# Peripherals.net
KiCad netlist of a schematic drawn in Altium Designer
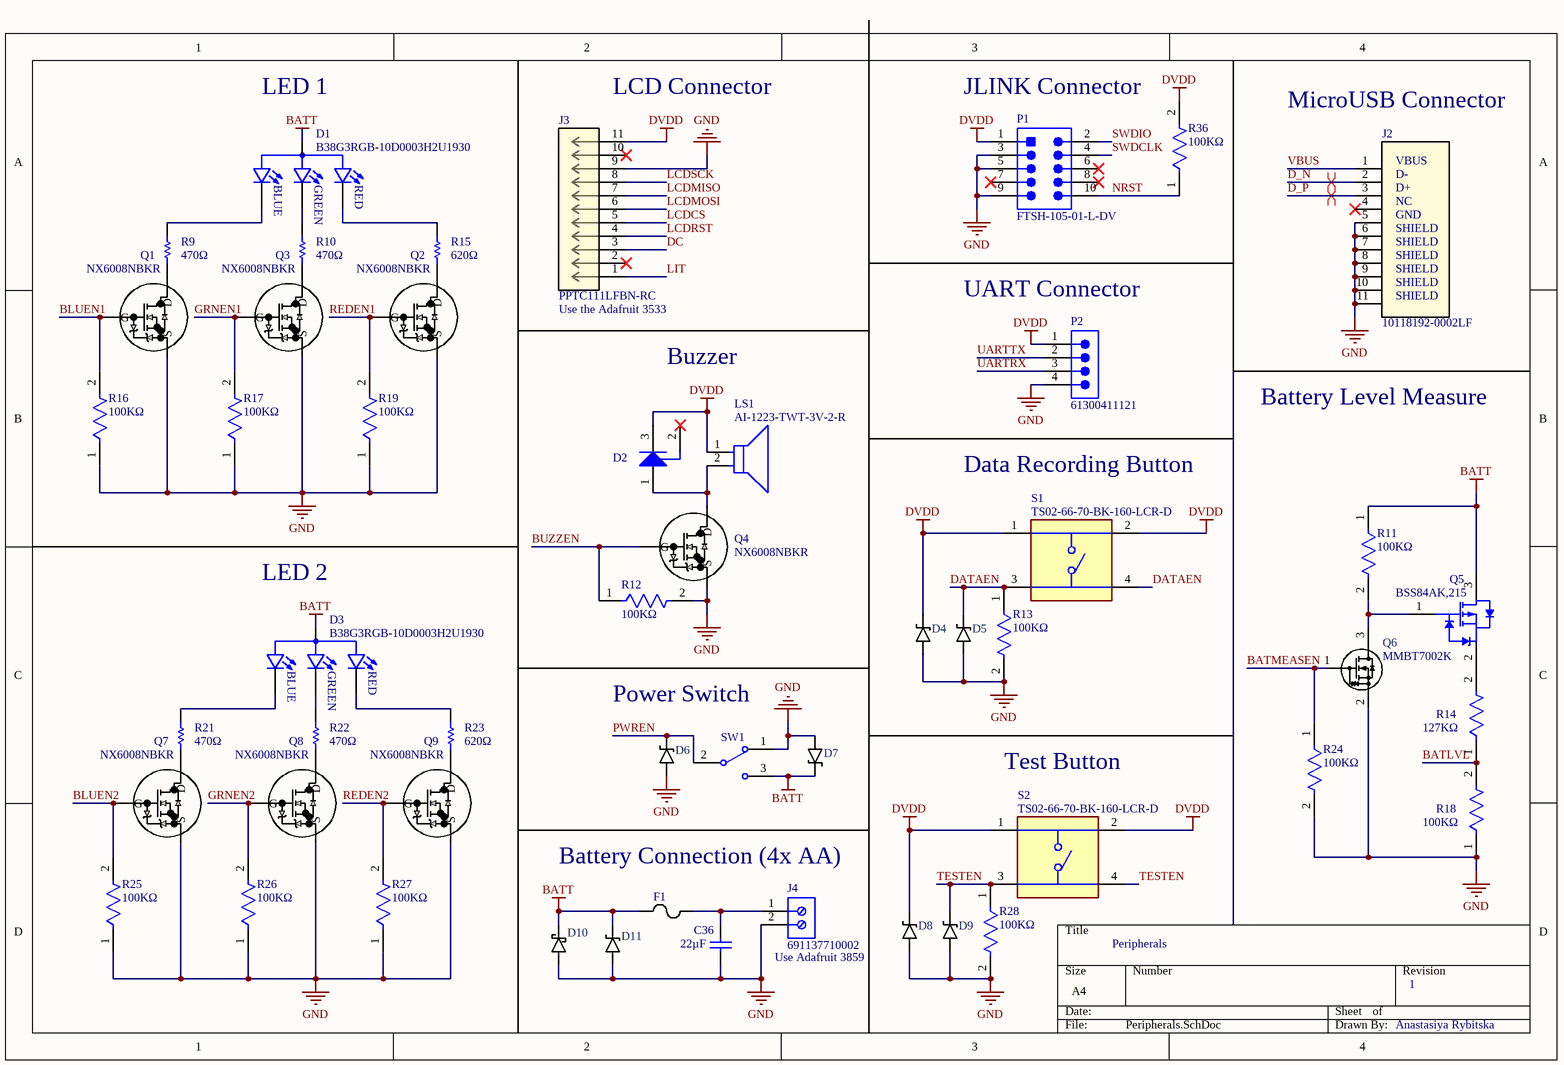
[diagram p0: Peripherals.SchDoc]

(export (version "E")
  (design (tool "Eeschema 10.0.6"))
  (components
    (comp (ref "C36")
      (value "TCJA226M016R0300E")
      (footprint "KEMT-1206-2_M")
      (description "CAP TANT POLY 22UF 16V 1206")
      (fields (field (name "CAPACITANCE") "22µF") (field (name "MANUFACTURER") "Kemet"))
      (libsource (lib "Altium Content Vault") (part "CAP-NP-2"))
    )
    (comp (ref "D1")
      (value "B38G3RGB-10D0003H2U1930")
      (footprint "LED_B38G3RGB-10D0003H2U1930")
      (description "Red, Green, Blue (RGB) - LED Indication - Discrete 2V Red, 3V Green, 3V Blue 0606 (1616 Metric)")
      (fields (field (name "MF") "Harvatek Corporation"))
      (libsource (lib "Schlib1") (part "B38G3RGB-10D0003H2U1930"))
    )
    (comp (ref "D2")
      (value "BAS16LT1G")
      (footprint "ONSC-SOT-23-3-318-08_V")
      (description "Switching Diode, 3-Pin SOT-23, Pb-Free, Tape and Reel")
      (fields (field (name "MANUFACTURER") "On Semiconductor"))
      (libsource (lib "Altium Content Vault") (part "ONSC-D-A1K3-3"))
    )
    (comp (ref "D3")
      (value "B38G3RGB-10D0003H2U1930")
      (footprint "LED_B38G3RGB-10D0003H2U1930")
      (description "Red, Green, Blue (RGB) - LED Indication - Discrete 2V Red, 3V Green, 3V Blue 0606 (1616 Metric)")
      (fields (field (name "MF") "Harvatek Corporation"))
      (libsource (lib "Schlib1") (part "B38G3RGB-10D0003H2U1930"))
    )
    (comp (ref "D4") (value "ESD5Z3V3") (footprint "SOD-523") (libsource (lib "Schlib1") (part "ESD5Z3V3")))
    (comp (ref "D5") (value "ESD5Z3V3") (footprint "SOD-523") (libsource (lib "Schlib1") (part "ESD5Z3V3")))
    (comp (ref "D6") (value "ESD5Z3V3") (footprint "SOD-523") (libsource (lib "Schlib1") (part "ESD5Z3V3")))
    (comp (ref "D7") (value "ESD5Z3V3") (footprint "SOD-523") (libsource (lib "Schlib1") (part "ESD5Z3V3")))
    (comp (ref "D8") (value "ESD5Z3V3") (footprint "SOD-523") (libsource (lib "Schlib1") (part "ESD5Z3V3")))
    (comp (ref "D9") (value "ESD5Z3V3") (footprint "SOD-523") (libsource (lib "Schlib1") (part "ESD5Z3V3")))
    (comp (ref "D10") (value "SK16") (footprint "DO-214AC_SMA") (libsource (lib "Schlib1") (part "SK16")))
    (comp (ref "D11") (value "ESD5Z3V3") (footprint "SOD-523") (libsource (lib "Schlib1") (part "ESD5Z3V3")))
    (comp (ref "F1")
      (value "MFU0603FF02000P500")
      (footprint "FUS_VISHAY_MFU0603_VIS")
      (description "No Description Available")
      (fields (field (name "COPYRIGHT") "Copyright (C) 2024 Ultra Librarian. All rights reserved."))
      (libsource (lib "Schlib1") (part "MFU0603FF02000P500"))
    )
    (comp (ref "J2")
      (value "10118192-0002LF")
      (footprint "CONN_10118192-0002LF_AMP")
      (description "No Description Available")
      (fields (field (name "COPYRIGHT") "Copyright (C) 2024 Ultra Librarian. All rights reserved."))
      (libsource (lib "Schlib1") (part "10118192-0002LF"))
    )
    (comp (ref "J3")
      (value "PPTC111LFBN-RC")
      (footprint "CONN11_PPPN111_SUL")
      (description "No Description Available")
      (fields (field (name "COPYRIGHT") "Copyright (C) 2023 Ultra Librarian. All rights reserved."))
      (libsource (lib "Schlib1") (part "PPTC111LFBN-RC"))
    )
    (comp (ref "J4")
      (value "691137710002")
      (footprint "691137710002")
      (libsource (lib "Altium Content Vault") (part "TBL - 1R - 02P - Screw"))
    )
    (comp (ref "LS1")
      (value "AI-1223-TWT-3V-2-R")
      (footprint "FP-AI-1223-TWT-3V-2-R-MFG")
      (description "BUZZER MAGNETIC 3V 12MM TH")
      (libsource (lib "Altium Content Vault") (part "1973c4b650225fd2ddacaff6b763965"))
    )
    (comp (ref "P1")
      (value "FTSH-105-01-L-DV")
      (footprint "SMTC-FTSH-105-01-L-DV_V")
      (description "CONN HEADER SMD 10POS 1.27MM (get from Garmin, or order cheaper)")
      (fields (field (name "MANUFACTURER") "Samtec"))
      (libsource (lib "Altium Content Vault") (part "CN-2P-M-R10"))
    )
    (comp (ref "P2")
      (value "61300411121")
      (footprint "61300411121")
      (libsource (lib "Altium Content Vault") (part "Header_Male_1R_04P"))
    )
    (comp (ref "Q1")
      (value "NX6008NBKR")
      (footprint "NX6008NBKR_NEX")
      (description "No Description Available")
      (fields (field (name "COPYRIGHT") "Copyright (C) 2023 Ultra Librarian. All rights reserved."))
      (libsource (lib "Schlib1") (part "NX6008NBKR"))
    )
    (comp (ref "Q2")
      (value "NX6008NBKR")
      (footprint "NX6008NBKR_NEX")
      (description "No Description Available")
      (fields (field (name "COPYRIGHT") "Copyright (C) 2023 Ultra Librarian. All rights reserved."))
      (libsource (lib "Schlib1") (part "NX6008NBKR"))
    )
    (comp (ref "Q3")
      (value "NX6008NBKR")
      (footprint "NX6008NBKR_NEX")
      (description "No Description Available")
      (fields (field (name "COPYRIGHT") "Copyright (C) 2023 Ultra Librarian. All rights reserved."))
      (libsource (lib "Schlib1") (part "NX6008NBKR"))
    )
    (comp (ref "Q4")
      (value "NX6008NBKR")
      (footprint "NX6008NBKR_NEX")
      (description "No Description Available")
      (fields (field (name "COPYRIGHT") "Copyright (C) 2023 Ultra Librarian. All rights reserved."))
      (libsource (lib "Schlib1") (part "NX6008NBKR"))
    )
    (comp (ref "Q5")
      (value "BSS84AK,215")
      (footprint "NXP-SOT23_N")
      (description "P-Channel Trench MOSFET, -50 V, -0.18 A, -55 to 150 degC, 3-Pin SOT23, Tape and Reel")
      (fields (field (name "MANUFACTURER") "NXP Semiconductors"))
      (libsource (lib "Altium Content Vault") (part "NXP-PMOS-GSD-3_B"))
    )
    (comp (ref "Q6") (value "MMBT7002K") (footprint "SOT-23") (libsource (lib "Schlib1") (part "MMBT7002K")))
    (comp (ref "Q7")
      (value "NX6008NBKR")
      (footprint "NX6008NBKR_NEX")
      (description "No Description Available")
      (fields (field (name "COPYRIGHT") "Copyright (C) 2023 Ultra Librarian. All rights reserved."))
      (libsource (lib "Schlib1") (part "NX6008NBKR"))
    )
    (comp (ref "Q8")
      (value "NX6008NBKR")
      (footprint "NX6008NBKR_NEX")
      (description "No Description Available")
      (fields (field (name "COPYRIGHT") "Copyright (C) 2023 Ultra Librarian. All rights reserved."))
      (libsource (lib "Schlib1") (part "NX6008NBKR"))
    )
    (comp (ref "Q9")
      (value "NX6008NBKR")
      (footprint "NX6008NBKR_NEX")
      (description "No Description Available")
      (fields (field (name "COPYRIGHT") "Copyright (C) 2023 Ultra Librarian. All rights reserved."))
      (libsource (lib "Schlib1") (part "NX6008NBKR"))
    )
    (comp (ref "R9")
      (value "RC0603FR-13470RL")
      (footprint "RESC1608X55X25NL10T15")
      (fields (field (name "MANUFACTURER") "Yageo") (field (name "RESISTANCE") "470Ω"))
      (libsource (lib "Altium Content Vault") (part "RES"))
    )
    (comp (ref "R10")
      (value "RC0603FR-13470RL")
      (footprint "RESC1608X55X25NL10T15")
      (fields (field (name "MANUFACTURER") "Yageo") (field (name "RESISTANCE") "470Ω"))
      (libsource (lib "Altium Content Vault") (part "RES"))
    )
    (comp (ref "R11")
      (value "RMCF0603FT100K")
      (footprint "FP-RMCF0603-IPC_C")
      (description "100kΩ ±1% 0.1W 0603 Thick Film Chip Resistor AEC-Q200 compliant")
      (fields (field (name "TOLERANCE") "1%") (field (name "RESISTANCE") "100KΩ"))
      (libsource (lib "Altium Content Vault") (part "1029c3af85768c4190bb7ad29bc67b5"))
    )
    (comp (ref "R12")
      (value "RMCF0603FT100K")
      (footprint "FP-RMCF0603-IPC_C")
      (description "100kΩ ±1% 0.1W 0603 Thick Film Chip Resistor AEC-Q200 compliant")
      (fields (field (name "TOLERANCE") "1%") (field (name "RESISTANCE") "100KΩ"))
      (libsource (lib "Altium Content Vault") (part "1029c3af85768c4190bb7ad29bc67b5"))
    )
    (comp (ref "R13")
      (value "RMCF0603FT100K")
      (footprint "FP-RMCF0603-IPC_C")
      (description "100kΩ ±1% 0.1W 0603 Thick Film Chip Resistor AEC-Q200 compliant")
      (fields (field (name "TOLERANCE") "1%") (field (name "RESISTANCE") "100KΩ"))
      (libsource (lib "Altium Content Vault") (part "1029c3af85768c4190bb7ad29bc67b5"))
    )
    (comp (ref "R14")
      (value "RT0603FRE07127KL")
      (footprint "FP-RT0603-MFG")
      (description "RES SMD 127K OHM 1% 1/10W 0603")
      (fields
        (field (name "MANUFACTURER") "Yageo")
        (field (name "TOLERANCE") "0.01")
        (field (name "RESISTANCE") "127KΩ")
      )
      (libsource (lib "Altium Content Vault") (part "1029c3af85768c4190bb7ad29bc67b5"))
    )
    (comp (ref "R15")
      (value "RC0603JR-07620RL")
      (footprint "RESC1608X55X25LL10T15")
      (fields (field (name "MANUFACTURER") "Yageo") (field (name "RESISTANCE") "620Ω"))
      (libsource (lib "Altium Content Vault") (part "RES"))
    )
    (comp (ref "R16")
      (value "RMCF0603FT100K")
      (footprint "FP-RMCF0603-IPC_C")
      (description "100kΩ ±1% 0.1W 0603 Thick Film Chip Resistor AEC-Q200 compliant")
      (fields (field (name "TOLERANCE") "1%") (field (name "RESISTANCE") "100KΩ"))
      (libsource (lib "Altium Content Vault") (part "1029c3af85768c4190bb7ad29bc67b5"))
    )
    (comp (ref "R17")
      (value "RMCF0603FT100K")
      (footprint "FP-RMCF0603-IPC_C")
      (description "100kΩ ±1% 0.1W 0603 Thick Film Chip Resistor AEC-Q200 compliant")
      (fields (field (name "TOLERANCE") "1%") (field (name "RESISTANCE") "100KΩ"))
      (libsource (lib "Altium Content Vault") (part "1029c3af85768c4190bb7ad29bc67b5"))
    )
    (comp (ref "R18")
      (value "RMCF0603FT100K")
      (footprint "FP-RMCF0603-IPC_C")
      (description "100kΩ ±1% 0.1W 0603 Thick Film Chip Resistor AEC-Q200 compliant")
      (fields (field (name "TOLERANCE") "1%") (field (name "RESISTANCE") "100KΩ"))
      (libsource (lib "Altium Content Vault") (part "1029c3af85768c4190bb7ad29bc67b5"))
    )
    (comp (ref "R19")
      (value "RMCF0603FT100K")
      (footprint "FP-RMCF0603-IPC_C")
      (description "100kΩ ±1% 0.1W 0603 Thick Film Chip Resistor AEC-Q200 compliant")
      (fields (field (name "TOLERANCE") "1%") (field (name "RESISTANCE") "100KΩ"))
      (libsource (lib "Altium Content Vault") (part "1029c3af85768c4190bb7ad29bc67b5"))
    )
    (comp (ref "R21")
      (value "RC0603FR-13470RL")
      (footprint "RESC1608X55X25NL10T15")
      (fields (field (name "MANUFACTURER") "Yageo") (field (name "RESISTANCE") "470Ω"))
      (libsource (lib "Altium Content Vault") (part "RES"))
    )
    (comp (ref "R22")
      (value "RC0603FR-13470RL")
      (footprint "RESC1608X55X25NL10T15")
      (fields (field (name "MANUFACTURER") "Yageo") (field (name "RESISTANCE") "470Ω"))
      (libsource (lib "Altium Content Vault") (part "RES"))
    )
    (comp (ref "R23")
      (value "RC0603JR-07620RL")
      (footprint "RESC1608X55X25LL10T15")
      (fields (field (name "MANUFACTURER") "Yageo") (field (name "RESISTANCE") "620Ω"))
      (libsource (lib "Altium Content Vault") (part "RES"))
    )
    (comp (ref "R24")
      (value "RMCF0603FT100K")
      (footprint "FP-RMCF0603-IPC_C")
      (description "100kΩ ±1% 0.1W 0603 Thick Film Chip Resistor AEC-Q200 compliant")
      (fields (field (name "TOLERANCE") "1%") (field (name "RESISTANCE") "100KΩ"))
      (libsource (lib "Altium Content Vault") (part "1029c3af85768c4190bb7ad29bc67b5"))
    )
    (comp (ref "R25")
      (value "RMCF0603FT100K")
      (footprint "FP-RMCF0603-IPC_C")
      (description "100kΩ ±1% 0.1W 0603 Thick Film Chip Resistor AEC-Q200 compliant")
      (fields (field (name "TOLERANCE") "1%") (field (name "RESISTANCE") "100KΩ"))
      (libsource (lib "Altium Content Vault") (part "1029c3af85768c4190bb7ad29bc67b5"))
    )
    (comp (ref "R26")
      (value "RMCF0603FT100K")
      (footprint "FP-RMCF0603-IPC_C")
      (description "100kΩ ±1% 0.1W 0603 Thick Film Chip Resistor AEC-Q200 compliant")
      (fields (field (name "TOLERANCE") "1%") (field (name "RESISTANCE") "100KΩ"))
      (libsource (lib "Altium Content Vault") (part "1029c3af85768c4190bb7ad29bc67b5"))
    )
    (comp (ref "R27")
      (value "RMCF0603FT100K")
      (footprint "FP-RMCF0603-IPC_C")
      (description "100kΩ ±1% 0.1W 0603 Thick Film Chip Resistor AEC-Q200 compliant")
      (fields (field (name "TOLERANCE") "1%") (field (name "RESISTANCE") "100KΩ"))
      (libsource (lib "Altium Content Vault") (part "1029c3af85768c4190bb7ad29bc67b5"))
    )
    (comp (ref "R28")
      (value "RMCF0603FT100K")
      (footprint "FP-RMCF0603-IPC_C")
      (description "100kΩ ±1% 0.1W 0603 Thick Film Chip Resistor AEC-Q200 compliant")
      (fields (field (name "TOLERANCE") "1%") (field (name "RESISTANCE") "100KΩ"))
      (libsource (lib "Altium Content Vault") (part "1029c3af85768c4190bb7ad29bc67b5"))
    )
    (comp (ref "R36")
      (value "RMCF0603FT100K")
      (footprint "FP-RMCF0603-IPC_C")
      (description "100kΩ ±1% 0.1W 0603 Thick Film Chip Resistor AEC-Q200 compliant")
      (fields (field (name "TOLERANCE") "1%") (field (name "RESISTANCE") "100KΩ"))
      (libsource (lib "Altium Content Vault") (part "1029c3af85768c4190bb7ad29bc67b5"))
    )
    (comp (ref "S1")
      (value "TS02-66-70-BK-160-LCR-D")
      (footprint "SW_TS02-66-70-BK-160-LCR-D")
      (description "6 x 6 mm, 7 mm Actuator Height, 160 gf, Black, Long Crimped, Through Hole, SPST, Tactile Switch")
      (fields (field (name "MF") "CUI Devices"))
      (libsource (lib "Schlib1") (part "TS02-66-70-BK-160-LCR-D"))
    )
    (comp (ref "S2")
      (value "TS02-66-70-BK-160-LCR-D")
      (footprint "SW_TS02-66-70-BK-160-LCR-D")
      (description "6 x 6 mm, 7 mm Actuator Height, 160 gf, Black, Long Crimped, Through Hole, SPST, Tactile Switch")
      (fields (field (name "MF") "CUI Devices"))
      (libsource (lib "Schlib1") (part "TS02-66-70-BK-160-LCR-D"))
    )
    (comp (ref "SW1")
      (value "EG1218")
      (footprint "ESWI-EG1218_V")
      (description "Slide Switch, 500 V, -20 to 70 degC, 3-Pin THD, RoHS")
      (libsource (lib "Altium Content Vault") (part "SW-SPDT-3_B"))
    )
  )
  (nets
    (net (code "1") (name "/BATLVL") (class "Default")
      (node (ref "R14") (pin "1") (pinfunction "1_1") (pintype "passive"))
      (node (ref "R18") (pin "2") (pinfunction "2_2") (pintype "passive"))
    )
    (net (code "2") (name "/BATMEASEN") (class "Default")
      (node (ref "Q6") (pin "1") (pinfunction "G_1") (pintype "passive"))
      (node (ref "R24") (pin "1") (pinfunction "1_1") (pintype "passive"))
    )
    (net (code "3") (name "/BLUEN1") (class "Default")
      (node (ref "Q1") (pin "1") (pinfunction "G_1") (pintype "passive"))
      (node (ref "R16") (pin "2") (pinfunction "2_2") (pintype "passive"))
    )
    (net (code "4") (name "/BLUEN2") (class "Default")
      (node (ref "Q7") (pin "1") (pinfunction "G_1") (pintype "passive"))
      (node (ref "R25") (pin "2") (pinfunction "2_2") (pintype "passive"))
    )
    (net (code "5") (name "/BUZZEN") (class "Default")
      (node (ref "Q4") (pin "1") (pinfunction "G_1") (pintype "passive"))
      (node (ref "R12") (pin "1") (pinfunction "1_1") (pintype "passive"))
    )
    (net (code "6") (name "/DATAEN") (class "Default")
      (node (ref "D5") (pin "K") (pinfunction "K_K") (pintype "passive"))
      (node (ref "R13") (pin "1") (pinfunction "1_1") (pintype "passive"))
      (node (ref "S1") (pin "3") (pinfunction "3_3") (pintype "passive"))
      (node (ref "S1") (pin "4") (pinfunction "4_4") (pintype "passive"))
    )
    (net (code "7") (name "/DC") (class "Default")
      (node (ref "J3") (pin "3") (pinfunction "3_3") (pintype "passive"))
    )
    (net (code "8") (name "/D_N") (class "Default")
      (node (ref "J2") (pin "2") (pinfunction "2_2") (pintype "passive"))
    )
    (net (code "9") (name "/D_P") (class "Default")
      (node (ref "J2") (pin "3") (pinfunction "3_3") (pintype "passive"))
    )
    (net (code "10") (name "/GRNEN1") (class "Default")
      (node (ref "Q3") (pin "1") (pinfunction "G_1") (pintype "passive"))
      (node (ref "R17") (pin "2") (pinfunction "2_2") (pintype "passive"))
    )
    (net (code "11") (name "/GRNEN2") (class "Default")
      (node (ref "Q8") (pin "1") (pinfunction "G_1") (pintype "passive"))
      (node (ref "R26") (pin "2") (pinfunction "2_2") (pintype "passive"))
    )
    (net (code "12") (name "/LCDCS") (class "Default")
      (node (ref "J3") (pin "5") (pinfunction "5_5") (pintype "passive"))
    )
    (net (code "13") (name "/LCDMISO") (class "Default")
      (node (ref "J3") (pin "7") (pinfunction "7_7") (pintype "passive"))
    )
    (net (code "14") (name "/LCDMOSI") (class "Default")
      (node (ref "J3") (pin "6") (pinfunction "6_6") (pintype "passive"))
    )
    (net (code "15") (name "/LCDRST") (class "Default")
      (node (ref "J3") (pin "4") (pinfunction "4_4") (pintype "passive"))
    )
    (net (code "16") (name "/LCDSCK") (class "Default")
      (node (ref "J3") (pin "8") (pinfunction "8_8") (pintype "passive"))
    )
    (net (code "17") (name "/LIT") (class "Default")
      (node (ref "J3") (pin "1") (pinfunction "1_1") (pintype "passive"))
    )
    (net (code "18") (name "/NRST") (class "Default")
      (node (ref "P1") (pin "10") (pinfunction "10_10") (pintype "passive"))
      (node (ref "R36") (pin "1") (pinfunction "1_1") (pintype "passive"))
    )
    (net (code "19") (name "/PWREN") (class "Default")
      (node (ref "D6") (pin "K") (pinfunction "K_K") (pintype "passive"))
      (node (ref "SW1") (pin "2") (pinfunction "COM_2") (pintype "passive"))
    )
    (net (code "20") (name "/REDEN1") (class "Default")
      (node (ref "Q2") (pin "1") (pinfunction "G_1") (pintype "passive"))
      (node (ref "R19") (pin "2") (pinfunction "2_2") (pintype "passive"))
    )
    (net (code "21") (name "/REDEN2") (class "Default")
      (node (ref "Q9") (pin "1") (pinfunction "G_1") (pintype "passive"))
      (node (ref "R27") (pin "2") (pinfunction "2_2") (pintype "passive"))
    )
    (net (code "22") (name "/SWDCLK") (class "Default")
      (node (ref "P1") (pin "4") (pinfunction "4_4") (pintype "passive"))
    )
    (net (code "23") (name "/SWDIO") (class "Default")
      (node (ref "P1") (pin "2") (pinfunction "2_2") (pintype "passive"))
    )
    (net (code "24") (name "/TESTEN") (class "Default")
      (node (ref "D9") (pin "K") (pinfunction "K_K") (pintype "passive"))
      (node (ref "R28") (pin "1") (pinfunction "1_1") (pintype "passive"))
      (node (ref "S2") (pin "3") (pinfunction "3_3") (pintype "passive"))
      (node (ref "S2") (pin "4") (pinfunction "4_4") (pintype "passive"))
    )
    (net (code "25") (name "/UARTRX") (class "Default")
      (node (ref "P2") (pin "3") (pinfunction "3_3") (pintype "passive"))
    )
    (net (code "26") (name "/UARTTX") (class "Default")
      (node (ref "P2") (pin "2") (pinfunction "2_2") (pintype "passive"))
    )
    (net (code "27") (name "/VBUS") (class "Default")
      (node (ref "J2") (pin "1") (pinfunction "1_1") (pintype "passive"))
    )
    (net (code "28") (name "BATT") (class "Default")
      (node (ref "D1") (pin "3") (pinfunction "A_3") (pintype "passive"))
      (node (ref "D10") (pin "K") (pinfunction "K_K") (pintype "passive"))
      (node (ref "D11") (pin "K") (pinfunction "K_K") (pintype "passive"))
      (node (ref "D3") (pin "3") (pinfunction "A_3") (pintype "passive"))
      (node (ref "D7") (pin "K") (pinfunction "K_K") (pintype "passive"))
      (node (ref "F1") (pin "1") (pinfunction "1_1") (pintype "passive"))
      (node (ref "Q5") (pin "3") (pinfunction "D_3") (pintype "passive"))
      (node (ref "R11") (pin "1") (pinfunction "1_1") (pintype "passive"))
      (node (ref "SW1") (pin "3") (pinfunction "3_3") (pintype "passive"))
    )
    (net (code "29") (name "DVDD") (class "Default")
      (node (ref "D2") (pin "3") (pinfunction "K_3") (pintype "passive"))
      (node (ref "D4") (pin "K") (pinfunction "K_K") (pintype "passive"))
      (node (ref "D8") (pin "K") (pinfunction "K_K") (pintype "passive"))
      (node (ref "J3") (pin "11") (pinfunction "11_11") (pintype "passive"))
      (node (ref "LS1") (pin "1") (pinfunction "C_1") (pintype "passive"))
      (node (ref "P1") (pin "1") (pinfunction "1_1") (pintype "passive"))
      (node (ref "P2") (pin "1") (pinfunction "1_1") (pintype "passive"))
      (node (ref "R36") (pin "2") (pinfunction "2_2") (pintype "passive"))
      (node (ref "S1") (pin "1") (pinfunction "1_1") (pintype "passive"))
      (node (ref "S1") (pin "2") (pinfunction "2_2") (pintype "passive"))
      (node (ref "S2") (pin "1") (pinfunction "1_1") (pintype "passive"))
      (node (ref "S2") (pin "2") (pinfunction "2_2") (pintype "passive"))
    )
    (net (code "30") (name "GND") (class "Default")
      (node (ref "C36") (pin "1") (pinfunction "1_1") (pintype "passive"))
      (node (ref "D10") (pin "A") (pinfunction "A_A") (pintype "passive"))
      (node (ref "D11") (pin "A") (pinfunction "A_A") (pintype "passive"))
      (node (ref "D4") (pin "A") (pinfunction "A_A") (pintype "passive"))
      (node (ref "D5") (pin "A") (pinfunction "A_A") (pintype "passive"))
      (node (ref "D6") (pin "A") (pinfunction "A_A") (pintype "passive"))
      (node (ref "D7") (pin "A") (pinfunction "A_A") (pintype "passive"))
      (node (ref "D8") (pin "A") (pinfunction "A_A") (pintype "passive"))
      (node (ref "D9") (pin "A") (pinfunction "A_A") (pintype "passive"))
      (node (ref "J2") (pin "10") (pinfunction "10_10") (pintype "passive"))
      (node (ref "J2") (pin "11") (pinfunction "11_11") (pintype "passive"))
      (node (ref "J2") (pin "5") (pinfunction "5_5") (pintype "passive"))
      (node (ref "J2") (pin "6") (pinfunction "6_6") (pintype "passive"))
      (node (ref "J2") (pin "7") (pinfunction "7_7") (pintype "passive"))
      (node (ref "J2") (pin "8") (pinfunction "8_8") (pintype "passive"))
      (node (ref "J2") (pin "9") (pinfunction "9_9") (pintype "passive"))
      (node (ref "J3") (pin "9") (pinfunction "9_9") (pintype "passive"))
      (node (ref "J4") (pin "2") (pinfunction "2_2") (pintype "passive"))
      (node (ref "P1") (pin "3") (pinfunction "3_3") (pintype "passive"))
      (node (ref "P1") (pin "5") (pinfunction "5_5") (pintype "passive"))
      (node (ref "P1") (pin "9") (pinfunction "9_9") (pintype "passive"))
      (node (ref "P2") (pin "4") (pinfunction "4_4") (pintype "passive"))
      (node (ref "Q1") (pin "2") (pinfunction "S_2") (pintype "passive"))
      (node (ref "Q2") (pin "2") (pinfunction "S_2") (pintype "passive"))
      (node (ref "Q3") (pin "2") (pinfunction "S_2") (pintype "passive"))
      (node (ref "Q4") (pin "2") (pinfunction "S_2") (pintype "passive"))
      (node (ref "Q6") (pin "2") (pinfunction "S_2") (pintype "passive"))
      (node (ref "Q7") (pin "2") (pinfunction "S_2") (pintype "passive"))
      (node (ref "Q8") (pin "2") (pinfunction "S_2") (pintype "passive"))
      (node (ref "Q9") (pin "2") (pinfunction "S_2") (pintype "passive"))
      (node (ref "R12") (pin "2") (pinfunction "2_2") (pintype "passive"))
      (node (ref "R13") (pin "2") (pinfunction "2_2") (pintype "passive"))
      (node (ref "R16") (pin "1") (pinfunction "1_1") (pintype "passive"))
      (node (ref "R17") (pin "1") (pinfunction "1_1") (pintype "passive"))
      (node (ref "R18") (pin "1") (pinfunction "1_1") (pintype "passive"))
      (node (ref "R19") (pin "1") (pinfunction "1_1") (pintype "passive"))
      (node (ref "R24") (pin "2") (pinfunction "2_2") (pintype "passive"))
      (node (ref "R25") (pin "1") (pinfunction "1_1") (pintype "passive"))
      (node (ref "R26") (pin "1") (pinfunction "1_1") (pintype "passive"))
      (node (ref "R27") (pin "1") (pinfunction "1_1") (pintype "passive"))
      (node (ref "R28") (pin "2") (pinfunction "2_2") (pintype "passive"))
      (node (ref "SW1") (pin "1") (pinfunction "1_1") (pintype "passive"))
    )
    (net (code "31") (name "Net-(C36-Pad2)") (class "Default")
      (node (ref "C36") (pin "2") (pinfunction "2_2") (pintype "passive"))
      (node (ref "F1") (pin "2") (pinfunction "2_2") (pintype "passive"))
      (node (ref "J4") (pin "1") (pinfunction "1_1") (pintype "passive"))
    )
    (net (code "32") (name "Net-(D1-B_C)") (class "Default")
      (node (ref "D1") (pin "2") (pinfunction "B_C_2") (pintype "passive"))
      (node (ref "R9") (pin "2") (pinfunction "2_2") (pintype "passive"))
    )
    (net (code "33") (name "Net-(D1-G_C)") (class "Default")
      (node (ref "D1") (pin "1") (pinfunction "G_C_1") (pintype "passive"))
      (node (ref "R10") (pin "2") (pinfunction "2_2") (pintype "passive"))
    )
    (net (code "34") (name "Net-(D1-R_C)") (class "Default")
      (node (ref "D1") (pin "4") (pinfunction "R_C_4") (pintype "passive"))
      (node (ref "R15") (pin "2") (pinfunction "2_2") (pintype "passive"))
    )
    (net (code "35") (name "Net-(D2-A)") (class "Default")
      (node (ref "D2") (pin "1") (pinfunction "A_1") (pintype "passive"))
      (node (ref "LS1") (pin "2") (pinfunction "A_2") (pintype "passive"))
      (node (ref "Q4") (pin "3") (pinfunction "D_3") (pintype "passive"))
    )
    (net (code "36") (name "Net-(D3-B_C)") (class "Default")
      (node (ref "D3") (pin "2") (pinfunction "B_C_2") (pintype "passive"))
      (node (ref "R21") (pin "2") (pinfunction "2_2") (pintype "passive"))
    )
    (net (code "37") (name "Net-(D3-G_C)") (class "Default")
      (node (ref "D3") (pin "1") (pinfunction "G_C_1") (pintype "passive"))
      (node (ref "R22") (pin "2") (pinfunction "2_2") (pintype "passive"))
    )
    (net (code "38") (name "Net-(D3-R_C)") (class "Default")
      (node (ref "D3") (pin "4") (pinfunction "R_C_4") (pintype "passive"))
      (node (ref "R23") (pin "2") (pinfunction "2_2") (pintype "passive"))
    )
    (net (code "39") (name "Net-(Q1-D)") (class "Default")
      (node (ref "Q1") (pin "3") (pinfunction "D_3") (pintype "passive"))
      (node (ref "R9") (pin "1") (pinfunction "1_1") (pintype "passive"))
    )
    (net (code "40") (name "Net-(Q2-D)") (class "Default")
      (node (ref "Q2") (pin "3") (pinfunction "D_3") (pintype "passive"))
      (node (ref "R15") (pin "1") (pinfunction "1_1") (pintype "passive"))
    )
    (net (code "41") (name "Net-(Q3-D)") (class "Default")
      (node (ref "Q3") (pin "3") (pinfunction "D_3") (pintype "passive"))
      (node (ref "R10") (pin "1") (pinfunction "1_1") (pintype "passive"))
    )
    (net (code "42") (name "Net-(Q5-G)") (class "Default")
      (node (ref "Q5") (pin "1") (pinfunction "G_1") (pintype "passive"))
      (node (ref "Q6") (pin "3") (pinfunction "D_3") (pintype "passive"))
      (node (ref "R11") (pin "2") (pinfunction "2_2") (pintype "passive"))
    )
    (net (code "43") (name "Net-(Q5-S)") (class "Default")
      (node (ref "Q5") (pin "2") (pinfunction "S_2") (pintype "passive"))
      (node (ref "R14") (pin "2") (pinfunction "2_2") (pintype "passive"))
    )
    (net (code "44") (name "Net-(Q7-D)") (class "Default")
      (node (ref "Q7") (pin "3") (pinfunction "D_3") (pintype "passive"))
      (node (ref "R21") (pin "1") (pinfunction "1_1") (pintype "passive"))
    )
    (net (code "45") (name "Net-(Q8-D)") (class "Default")
      (node (ref "Q8") (pin "3") (pinfunction "D_3") (pintype "passive"))
      (node (ref "R22") (pin "1") (pinfunction "1_1") (pintype "passive"))
    )
    (net (code "46") (name "Net-(Q9-D)") (class "Default")
      (node (ref "Q9") (pin "3") (pinfunction "D_3") (pintype "passive"))
      (node (ref "R23") (pin "1") (pinfunction "1_1") (pintype "passive"))
    )
    (net (code "47") (name "unconnected-(D2-NC-Pad2)") (class "Default")
      (node (ref "D2") (pin "2") (pinfunction "NC_2") (pintype "passive+no_connect"))
    )
    (net (code "48") (name "unconnected-(J2-Pad4)") (class "Default")
      (node (ref "J2") (pin "4") (pinfunction "4_4") (pintype "passive+no_connect"))
    )
    (net (code "49") (name "unconnected-(J3-Pad2)") (class "Default")
      (node (ref "J3") (pin "2") (pinfunction "2_2") (pintype "passive+no_connect"))
    )
    (net (code "50") (name "unconnected-(J3-Pad10)") (class "Default")
      (node (ref "J3") (pin "10") (pinfunction "10_10") (pintype "passive+no_connect"))
    )
    (net (code "51") (name "unconnected-(P1-Pad6)") (class "Default")
      (node (ref "P1") (pin "6") (pinfunction "6_6") (pintype "passive+no_connect"))
    )
    (net (code "52") (name "unconnected-(P1-Pad7)") (class "Default")
      (node (ref "P1") (pin "7") (pinfunction "7_7") (pintype "passive+no_connect"))
    )
    (net (code "53") (name "unconnected-(P1-Pad8)") (class "Default")
      (node (ref "P1") (pin "8") (pinfunction "8_8") (pintype "passive+no_connect"))
    )
  )
)
